# SuperCapV0.net
KiCad netlist of a schematic drawn in Altium Designer
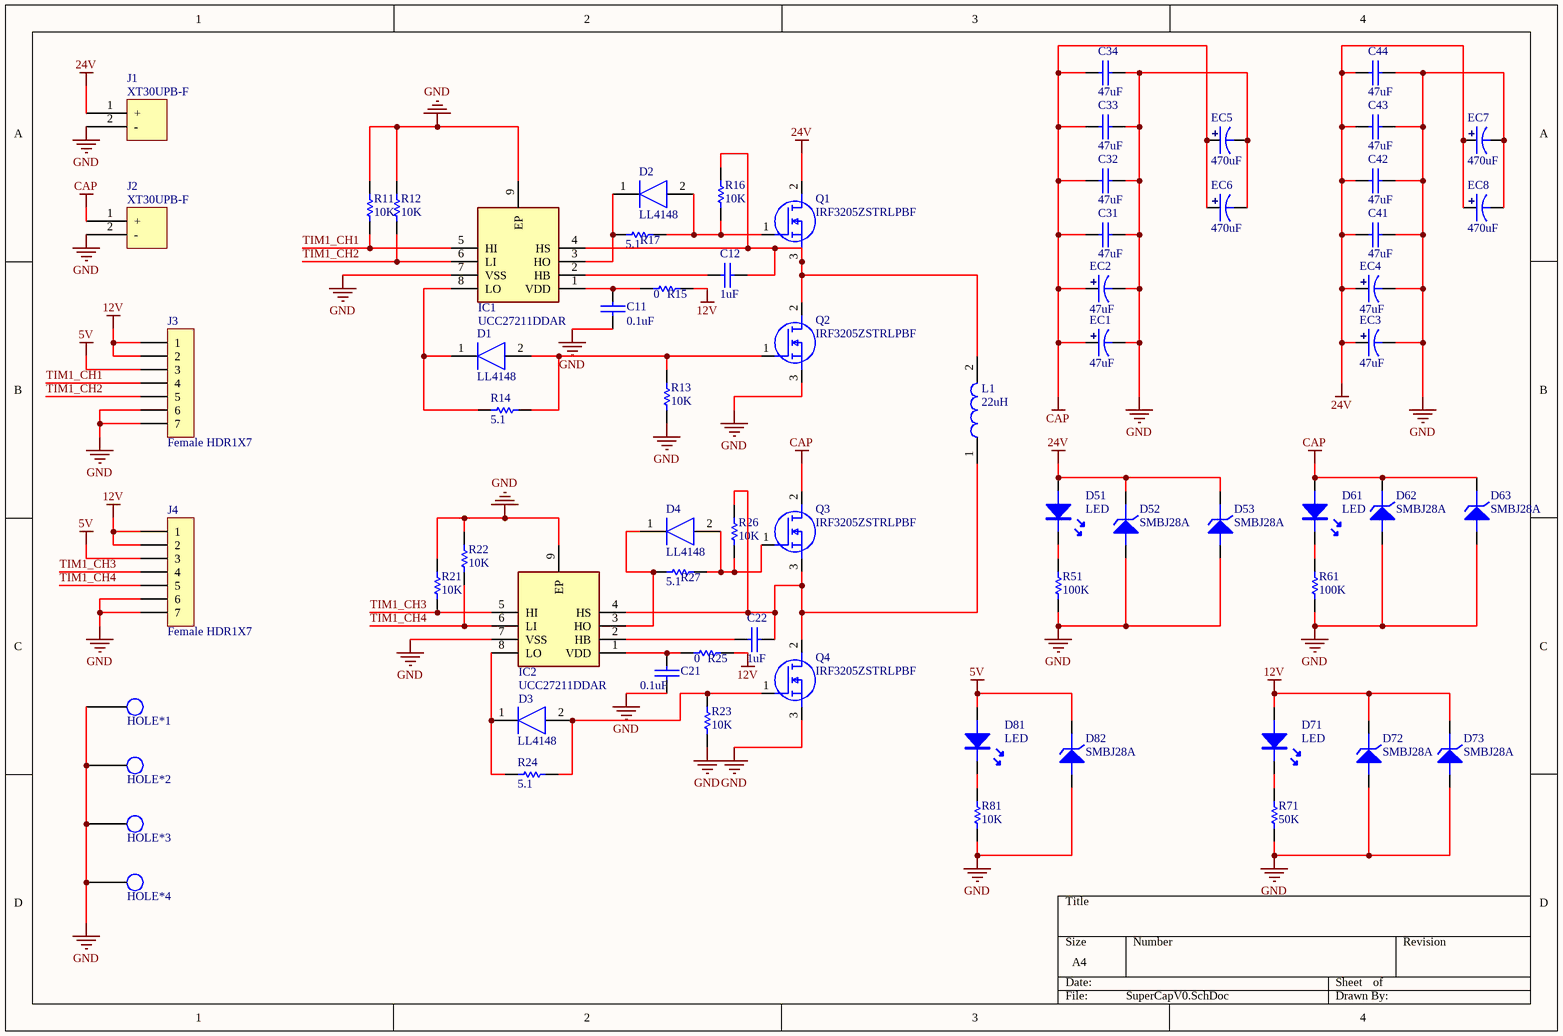
[diagram p0: SuperCapV0.SchDoc]

(export (version "E")
  (design (tool "Eeschema 10.0.6"))
  (components
    (comp (ref "C11")
      (value "0.1uF")
      (footprint "0603C")
      (description "无极性电容")
      (libsource (lib "电容") (part "CAP"))
    )
    (comp (ref "C12")
      (value "1uF")
      (footprint "0603C")
      (description "无极性电容")
      (libsource (lib "电容") (part "CAP"))
    )
    (comp (ref "C21")
      (value "0.1uF")
      (footprint "0603C")
      (description "无极性电容")
      (libsource (lib "电容") (part "CAP"))
    )
    (comp (ref "C22")
      (value "1uF")
      (footprint "0603C")
      (description "无极性电容")
      (libsource (lib "电容") (part "CAP"))
    )
    (comp (ref "C31")
      (value "47uF")
      (footprint "1812C")
      (description "无极性电容")
      (libsource (lib "电容") (part "CAP"))
    )
    (comp (ref "C32")
      (value "47uF")
      (footprint "1812C")
      (description "无极性电容")
      (libsource (lib "电容") (part "CAP"))
    )
    (comp (ref "C33")
      (value "47uF")
      (footprint "1812C")
      (description "无极性电容")
      (libsource (lib "电容") (part "CAP"))
    )
    (comp (ref "C34")
      (value "47uF")
      (footprint "1812C")
      (description "无极性电容")
      (libsource (lib "电容") (part "CAP"))
    )
    (comp (ref "C41")
      (value "47uF")
      (footprint "1812C")
      (description "无极性电容")
      (libsource (lib "电容") (part "CAP"))
    )
    (comp (ref "C42")
      (value "47uF")
      (footprint "1812C")
      (description "无极性电容")
      (libsource (lib "电容") (part "CAP"))
    )
    (comp (ref "C43")
      (value "47uF")
      (footprint "1812C")
      (description "无极性电容")
      (libsource (lib "电容") (part "CAP"))
    )
    (comp (ref "C44")
      (value "47uF")
      (footprint "1812C")
      (description "无极性电容")
      (libsource (lib "电容") (part "CAP"))
    )
    (comp (ref "D1")
      (value "LL4148")
      (footprint "SamacSys:FDLL4448")
      (description "Diode")
      (fields (field (name "MOUSER PART NUMBER") "512-LL4148"))
      (libsource (lib "*") (part "LL4148"))
    )
    (comp (ref "D2")
      (value "LL4148")
      (footprint "SamacSys:FDLL4448")
      (description "Diode")
      (fields (field (name "MOUSER PART NUMBER") "512-LL4148"))
      (libsource (lib "*") (part "LL4148"))
    )
    (comp (ref "D3")
      (value "LL4148")
      (footprint "SamacSys:FDLL4448")
      (description "Diode")
      (fields (field (name "MOUSER PART NUMBER") "512-LL4148"))
      (libsource (lib "*") (part "LL4148"))
    )
    (comp (ref "D4")
      (value "LL4148")
      (footprint "SamacSys:FDLL4448")
      (description "Diode")
      (fields (field (name "MOUSER PART NUMBER") "512-LL4148"))
      (libsource (lib "*") (part "LL4148"))
    )
    (comp (ref "D51") (value "LED") (footprint "LED-0603G") (libsource (lib "SuperCap_V2") (part "LED")))
    (comp (ref "D52")
      (value "SMBJ28A")
      (footprint "SMC/DO-214AB")
      (description "稳压二极管")
      (libsource (lib "二极管") (part "DIODE ZENER"))
    )
    (comp (ref "D53")
      (value "SMBJ28A")
      (footprint "SMC/DO-214AB")
      (description "稳压二极管")
      (libsource (lib "二极管") (part "DIODE ZENER"))
    )
    (comp (ref "D61") (value "LED") (footprint "LED-0603G") (libsource (lib "SuperCap_V2") (part "LED")))
    (comp (ref "D62")
      (value "SMBJ28A")
      (footprint "SMC/DO-214AB")
      (description "稳压二极管")
      (libsource (lib "二极管") (part "DIODE ZENER"))
    )
    (comp (ref "D63")
      (value "SMBJ28A")
      (footprint "SMC/DO-214AB")
      (description "稳压二极管")
      (libsource (lib "二极管") (part "DIODE ZENER"))
    )
    (comp (ref "D71") (value "LED") (footprint "LED-0603G") (libsource (lib "SuperCap_V2") (part "LED")))
    (comp (ref "D72")
      (value "SMBJ28A")
      (footprint "SMC/DO-214AB")
      (description "稳压二极管")
      (libsource (lib "二极管") (part "DIODE ZENER"))
    )
    (comp (ref "D73")
      (value "SMBJ28A")
      (footprint "SMC/DO-214AB")
      (description "稳压二极管")
      (libsource (lib "二极管") (part "DIODE ZENER"))
    )
    (comp (ref "D81") (value "LED") (footprint "LED-0603G") (libsource (lib "SuperCap_V2") (part "LED")))
    (comp (ref "D82")
      (value "SMBJ28A")
      (footprint "SMC/DO-214AB")
      (description "稳压二极管")
      (libsource (lib "二极管") (part "DIODE ZENER"))
    )
    (comp (ref "EC1")
      (value "47uF")
      (footprint "SMD-EC10X10X10")
      (description "贴片电解电容")
      (libsource (lib "电容") (part "SMD_ECAP"))
    )
    (comp (ref "EC2")
      (value "47uF")
      (footprint "SMD-EC10X10X10")
      (description "贴片电解电容")
      (libsource (lib "电容") (part "SMD_ECAP"))
    )
    (comp (ref "EC3")
      (value "47uF")
      (footprint "SMD-EC10X10X10")
      (description "贴片电解电容")
      (libsource (lib "电容") (part "SMD_ECAP"))
    )
    (comp (ref "EC4")
      (value "47uF")
      (footprint "SMD-EC10X10X10")
      (description "贴片电解电容")
      (libsource (lib "电容") (part "SMD_ECAP"))
    )
    (comp (ref "EC5")
      (value "470uF")
      (footprint "DIP-EC5.0X10X16-A")
      (description "直插电解电容")
      (libsource (lib "电容") (part "DIP_ECAP"))
    )
    (comp (ref "EC6")
      (value "470uF")
      (footprint "DIP-EC5.0X10X16-A")
      (description "直插电解电容")
      (libsource (lib "电容") (part "DIP_ECAP"))
    )
    (comp (ref "EC7")
      (value "470uF")
      (footprint "DIP-EC5.0X10X16-A")
      (description "直插电解电容")
      (libsource (lib "电容") (part "DIP_ECAP"))
    )
    (comp (ref "EC8")
      (value "470uF")
      (footprint "DIP-EC5.0X10X16-A")
      (description "直插电解电容")
      (libsource (lib "电容") (part "DIP_ECAP"))
    )
    (comp (ref "HOLE*1") (value "Hole") (footprint "M3") (libsource (lib "SuperCap_V2") (part "Hole")))
    (comp (ref "HOLE*2") (value "Hole") (footprint "M3") (libsource (lib "SuperCap_V2") (part "Hole")))
    (comp (ref "HOLE*3") (value "Hole") (footprint "M3") (libsource (lib "SuperCap_V2") (part "Hole")))
    (comp (ref "HOLE*4") (value "Hole") (footprint "M3") (libsource (lib "SuperCap_V2") (part "Hole")))
    (comp (ref "IC1")
      (value "UCC27211DDAR")
      (footprint "SamacSys:SOIC127P600X170-9N")
      (description "Integrated Circuit")
      (fields (field (name "MOUSER PART NUMBER") "595-UCC27211DDAR"))
      (libsource (lib "SamacSys") (part "UCC27211DDAR"))
    )
    (comp (ref "IC2")
      (value "UCC27211DDAR")
      (footprint "SamacSys:SOIC127P600X170-9N")
      (description "Integrated Circuit")
      (fields (field (name "MOUSER PART NUMBER") "595-UCC27211DDAR"))
      (libsource (lib "SamacSys") (part "UCC27211DDAR"))
    )
    (comp (ref "J1")
      (value "XT30UPB-F")
      (footprint "XT30UPB-F")
      (libsource (lib "powerdesigner") (part "XT30UPB-F"))
    )
    (comp (ref "J2")
      (value "XT30UPB-F")
      (footprint "XT30UPB-F")
      (libsource (lib "powerdesigner") (part "XT30UPB-F"))
    )
    (comp (ref "J3")
      (value "Female HDR1X7")
      (footprint "Fe-HDR1X7/2.54-S")
      (libsource (lib "排母") (part "Female HDR1X7"))
    )
    (comp (ref "J4")
      (value "Female HDR1X7")
      (footprint "Fe-HDR1X7/2.54-S")
      (libsource (lib "排母") (part "Female HDR1X7"))
    )
    (comp (ref "L1")
      (value "22uH")
      (footprint "SamacSys:INDPM180170X700N")
      (description "Inductor")
      (fields (field (name "MANUFACTURER_PART_NUMBER") "BCIHP1770-100M"))
      (libsource (lib "SuperCap_V2") (part "BCIHP1770-100M"))
    )
    (comp (ref "Q1")
      (value "IRF3205ZSTRLPBF")
      (footprint "SamacSys:IDB30E60")
      (description "MOSFET (N-Channel)")
      (fields (field (name "MOUSER PART NUMBER") "942-IRF3205ZSTRLPBF"))
      (libsource (lib "SamacSys") (part "IRF3205ZSTRLPBF"))
    )
    (comp (ref "Q2")
      (value "IRF3205ZSTRLPBF")
      (footprint "SamacSys:IDB30E60")
      (description "MOSFET (N-Channel)")
      (fields (field (name "MOUSER PART NUMBER") "942-IRF3205ZSTRLPBF"))
      (libsource (lib "SamacSys") (part "IRF3205ZSTRLPBF"))
    )
    (comp (ref "Q3")
      (value "IRF3205ZSTRLPBF")
      (footprint "SamacSys:IDB30E60")
      (description "MOSFET (N-Channel)")
      (fields (field (name "MOUSER PART NUMBER") "942-IRF3205ZSTRLPBF"))
      (libsource (lib "SamacSys") (part "IRF3205ZSTRLPBF"))
    )
    (comp (ref "Q4")
      (value "IRF3205ZSTRLPBF")
      (footprint "SamacSys:IDB30E60")
      (description "MOSFET (N-Channel)")
      (fields (field (name "MOUSER PART NUMBER") "942-IRF3205ZSTRLPBF"))
      (libsource (lib "SamacSys") (part "IRF3205ZSTRLPBF"))
    )
    (comp (ref "R11") (value "10K") (footprint "0603R") (libsource (lib "电阻") (part "RES")))
    (comp (ref "R12") (value "10K") (footprint "0603R") (libsource (lib "电阻") (part "RES")))
    (comp (ref "R13") (value "10K") (footprint "0603R") (libsource (lib "电阻") (part "RES")))
    (comp (ref "R14") (value "5.1") (footprint "0603R") (libsource (lib "电阻") (part "RES")))
    (comp (ref "R15") (value "0") (footprint "0603R") (libsource (lib "电阻") (part "RES")))
    (comp (ref "R16") (value "10K") (footprint "0603R") (libsource (lib "电阻") (part "RES")))
    (comp (ref "R17") (value "5.1") (footprint "0603R") (libsource (lib "电阻") (part "RES")))
    (comp (ref "R21") (value "10K") (footprint "0603R") (libsource (lib "电阻") (part "RES")))
    (comp (ref "R22") (value "10K") (footprint "0603R") (libsource (lib "电阻") (part "RES")))
    (comp (ref "R23") (value "10K") (footprint "0603R") (libsource (lib "电阻") (part "RES")))
    (comp (ref "R24") (value "5.1") (footprint "0603R") (libsource (lib "电阻") (part "RES")))
    (comp (ref "R25") (value "0") (footprint "0603R") (libsource (lib "电阻") (part "RES")))
    (comp (ref "R26") (value "10K") (footprint "0603R") (libsource (lib "电阻") (part "RES")))
    (comp (ref "R27") (value "5.1") (footprint "0603R") (libsource (lib "电阻") (part "RES")))
    (comp (ref "R51") (value "100K") (footprint "0603R") (libsource (lib "电阻") (part "RES")))
    (comp (ref "R61") (value "100K") (footprint "0603R") (libsource (lib "电阻") (part "RES")))
    (comp (ref "R71") (value "50K") (footprint "0603R") (libsource (lib "电阻") (part "RES")))
    (comp (ref "R81") (value "10K") (footprint "0603R") (libsource (lib "电阻") (part "RES")))
  )
  (nets
    (net (code "1") (name "/TIM1_CH1") (class "Default")
      (node (ref "IC1") (pin "5") (pinfunction "HI_5") (pintype "passive"))
      (node (ref "J3") (pin "4") (pinfunction "4_4") (pintype "passive"))
      (node (ref "R11") (pin "1") (pinfunction "1_1") (pintype "passive"))
    )
    (net (code "2") (name "/TIM1_CH2") (class "Default")
      (node (ref "IC1") (pin "6") (pinfunction "LI_6") (pintype "passive"))
      (node (ref "J3") (pin "5") (pinfunction "5_5") (pintype "passive"))
      (node (ref "R12") (pin "1") (pinfunction "1_1") (pintype "passive"))
    )
    (net (code "3") (name "/TIM1_CH3") (class "Default")
      (node (ref "IC2") (pin "5") (pinfunction "HI_5") (pintype "passive"))
      (node (ref "J4") (pin "4") (pinfunction "4_4") (pintype "passive"))
      (node (ref "R21") (pin "1") (pinfunction "1_1") (pintype "passive"))
    )
    (net (code "4") (name "/TIM1_CH4") (class "Default")
      (node (ref "IC2") (pin "6") (pinfunction "LI_6") (pintype "passive"))
      (node (ref "J4") (pin "5") (pinfunction "5_5") (pintype "passive"))
      (node (ref "R22") (pin "1") (pinfunction "1_1") (pintype "passive"))
    )
    (net (code "5") (name "5V") (class "Default")
      (node (ref "D81") (pin "A") (pinfunction "A_A") (pintype "passive"))
      (node (ref "D82") (pin "K") (pinfunction "K_K") (pintype "passive"))
      (node (ref "J3") (pin "3") (pinfunction "3_3") (pintype "passive"))
      (node (ref "J4") (pin "3") (pinfunction "3_3") (pintype "passive"))
    )
    (net (code "6") (name "12V") (class "Default")
      (node (ref "D71") (pin "A") (pinfunction "A_A") (pintype "passive"))
      (node (ref "D72") (pin "K") (pinfunction "K_K") (pintype "passive"))
      (node (ref "D73") (pin "K") (pinfunction "K_K") (pintype "passive"))
      (node (ref "J3") (pin "1") (pinfunction "1_1") (pintype "passive"))
      (node (ref "J3") (pin "2") (pinfunction "2_2") (pintype "passive"))
      (node (ref "J4") (pin "1") (pinfunction "1_1") (pintype "passive"))
      (node (ref "J4") (pin "2") (pinfunction "2_2") (pintype "passive"))
      (node (ref "R15") (pin "2") (pinfunction "2_2") (pintype "passive"))
      (node (ref "R25") (pin "2") (pinfunction "2_2") (pintype "passive"))
    )
    (net (code "7") (name "24V") (class "Default")
      (node (ref "C41") (pin "1") (pinfunction "1_1") (pintype "passive"))
      (node (ref "C42") (pin "1") (pinfunction "1_1") (pintype "passive"))
      (node (ref "C43") (pin "1") (pinfunction "1_1") (pintype "passive"))
      (node (ref "C44") (pin "1") (pinfunction "1_1") (pintype "passive"))
      (node (ref "D51") (pin "A") (pinfunction "A_A") (pintype "passive"))
      (node (ref "D52") (pin "K") (pinfunction "K_K") (pintype "passive"))
      (node (ref "D53") (pin "K") (pinfunction "K_K") (pintype "passive"))
      (node (ref "EC3") (pin "1") (pinfunction "1_1") (pintype "passive"))
      (node (ref "EC4") (pin "1") (pinfunction "1_1") (pintype "passive"))
      (node (ref "EC7") (pin "1") (pinfunction "1_1") (pintype "passive"))
      (node (ref "EC8") (pin "1") (pinfunction "1_1") (pintype "passive"))
      (node (ref "J1") (pin "1") (pinfunction "+_1") (pintype "passive"))
      (node (ref "Q1") (pin "2") (pinfunction "D_2") (pintype "passive"))
    )
    (net (code "8") (name "CAP") (class "Default")
      (node (ref "C31") (pin "1") (pinfunction "1_1") (pintype "passive"))
      (node (ref "C32") (pin "1") (pinfunction "1_1") (pintype "passive"))
      (node (ref "C33") (pin "1") (pinfunction "1_1") (pintype "passive"))
      (node (ref "C34") (pin "1") (pinfunction "1_1") (pintype "passive"))
      (node (ref "D61") (pin "A") (pinfunction "A_A") (pintype "passive"))
      (node (ref "D62") (pin "K") (pinfunction "K_K") (pintype "passive"))
      (node (ref "D63") (pin "K") (pinfunction "K_K") (pintype "passive"))
      (node (ref "EC1") (pin "1") (pinfunction "1_1") (pintype "passive"))
      (node (ref "EC2") (pin "1") (pinfunction "1_1") (pintype "passive"))
      (node (ref "EC5") (pin "1") (pinfunction "1_1") (pintype "passive"))
      (node (ref "EC6") (pin "1") (pinfunction "1_1") (pintype "passive"))
      (node (ref "J2") (pin "1") (pinfunction "+_1") (pintype "passive"))
      (node (ref "Q3") (pin "2") (pinfunction "D_2") (pintype "passive"))
    )
    (net (code "9") (name "GND") (class "Default")
      (node (ref "C11") (pin "1") (pinfunction "1_1") (pintype "passive"))
      (node (ref "C21") (pin "1") (pinfunction "1_1") (pintype "passive"))
      (node (ref "C31") (pin "2") (pinfunction "2_2") (pintype "passive"))
      (node (ref "C32") (pin "2") (pinfunction "2_2") (pintype "passive"))
      (node (ref "C33") (pin "2") (pinfunction "2_2") (pintype "passive"))
      (node (ref "C34") (pin "2") (pinfunction "2_2") (pintype "passive"))
      (node (ref "C41") (pin "2") (pinfunction "2_2") (pintype "passive"))
      (node (ref "C42") (pin "2") (pinfunction "2_2") (pintype "passive"))
      (node (ref "C43") (pin "2") (pinfunction "2_2") (pintype "passive"))
      (node (ref "C44") (pin "2") (pinfunction "2_2") (pintype "passive"))
      (node (ref "D52") (pin "A") (pinfunction "A_A") (pintype "passive"))
      (node (ref "D53") (pin "A") (pinfunction "A_A") (pintype "passive"))
      (node (ref "D62") (pin "A") (pinfunction "A_A") (pintype "passive"))
      (node (ref "D63") (pin "A") (pinfunction "A_A") (pintype "passive"))
      (node (ref "D72") (pin "A") (pinfunction "A_A") (pintype "passive"))
      (node (ref "D73") (pin "A") (pinfunction "A_A") (pintype "passive"))
      (node (ref "D82") (pin "A") (pinfunction "A_A") (pintype "passive"))
      (node (ref "EC1") (pin "2") (pinfunction "2_2") (pintype "passive"))
      (node (ref "EC2") (pin "2") (pinfunction "2_2") (pintype "passive"))
      (node (ref "EC3") (pin "2") (pinfunction "2_2") (pintype "passive"))
      (node (ref "EC4") (pin "2") (pinfunction "2_2") (pintype "passive"))
      (node (ref "EC5") (pin "2") (pinfunction "2_2") (pintype "passive"))
      (node (ref "EC6") (pin "2") (pinfunction "2_2") (pintype "passive"))
      (node (ref "EC7") (pin "2") (pinfunction "2_2") (pintype "passive"))
      (node (ref "EC8") (pin "2") (pinfunction "2_2") (pintype "passive"))
      (node (ref "HOLE*1") (pin "1") (pinfunction "1_1") (pintype "passive"))
      (node (ref "HOLE*2") (pin "1") (pinfunction "1_1") (pintype "passive"))
      (node (ref "HOLE*3") (pin "1") (pinfunction "1_1") (pintype "passive"))
      (node (ref "HOLE*4") (pin "1") (pinfunction "1_1") (pintype "passive"))
      (node (ref "IC1") (pin "7") (pinfunction "VSS_7") (pintype "passive"))
      (node (ref "IC1") (pin "9") (pinfunction "EP_9") (pintype "passive"))
      (node (ref "IC2") (pin "7") (pinfunction "VSS_7") (pintype "passive"))
      (node (ref "IC2") (pin "9") (pinfunction "EP_9") (pintype "passive"))
      (node (ref "J1") (pin "2") (pinfunction "-_2") (pintype "passive"))
      (node (ref "J2") (pin "2") (pinfunction "-_2") (pintype "passive"))
      (node (ref "J3") (pin "6") (pinfunction "6_6") (pintype "passive"))
      (node (ref "J3") (pin "7") (pinfunction "7_7") (pintype "passive"))
      (node (ref "J4") (pin "6") (pinfunction "6_6") (pintype "passive"))
      (node (ref "J4") (pin "7") (pinfunction "7_7") (pintype "passive"))
      (node (ref "Q2") (pin "3") (pinfunction "S_3") (pintype "passive"))
      (node (ref "Q4") (pin "3") (pinfunction "S_3") (pintype "passive"))
      (node (ref "R11") (pin "2") (pinfunction "2_2") (pintype "passive"))
      (node (ref "R12") (pin "2") (pinfunction "2_2") (pintype "passive"))
      (node (ref "R13") (pin "1") (pinfunction "1_1") (pintype "passive"))
      (node (ref "R21") (pin "2") (pinfunction "2_2") (pintype "passive"))
      (node (ref "R22") (pin "2") (pinfunction "2_2") (pintype "passive"))
      (node (ref "R23") (pin "1") (pinfunction "1_1") (pintype "passive"))
      (node (ref "R51") (pin "1") (pinfunction "1_1") (pintype "passive"))
      (node (ref "R61") (pin "1") (pinfunction "1_1") (pintype "passive"))
      (node (ref "R71") (pin "1") (pinfunction "1_1") (pintype "passive"))
      (node (ref "R81") (pin "1") (pinfunction "1_1") (pintype "passive"))
    )
    (net (code "10") (name "Net-(D1-A)") (class "Default")
      (node (ref "D1") (pin "2") (pinfunction "A_2") (pintype "passive"))
      (node (ref "Q2") (pin "1") (pinfunction "G_1") (pintype "passive"))
      (node (ref "R13") (pin "2") (pinfunction "2_2") (pintype "passive"))
      (node (ref "R14") (pin "2") (pinfunction "2_2") (pintype "passive"))
    )
    (net (code "11") (name "Net-(D1-K)") (class "Default")
      (node (ref "D1") (pin "1") (pinfunction "K_1") (pintype "passive"))
      (node (ref "IC1") (pin "8") (pinfunction "LO_8") (pintype "passive"))
      (node (ref "R14") (pin "1") (pinfunction "1_1") (pintype "passive"))
    )
    (net (code "12") (name "Net-(D2-A)") (class "Default")
      (node (ref "D2") (pin "2") (pinfunction "A_2") (pintype "passive"))
      (node (ref "Q1") (pin "1") (pinfunction "G_1") (pintype "passive"))
      (node (ref "R16") (pin "1") (pinfunction "1_1") (pintype "passive"))
      (node (ref "R17") (pin "2") (pinfunction "2_2") (pintype "passive"))
    )
    (net (code "13") (name "Net-(D2-K)") (class "Default")
      (node (ref "D2") (pin "1") (pinfunction "K_1") (pintype "passive"))
      (node (ref "IC1") (pin "3") (pinfunction "HO_3") (pintype "passive"))
      (node (ref "R17") (pin "1") (pinfunction "1_1") (pintype "passive"))
    )
    (net (code "14") (name "Net-(D3-A)") (class "Default")
      (node (ref "D3") (pin "2") (pinfunction "A_2") (pintype "passive"))
      (node (ref "Q4") (pin "1") (pinfunction "G_1") (pintype "passive"))
      (node (ref "R23") (pin "2") (pinfunction "2_2") (pintype "passive"))
      (node (ref "R24") (pin "2") (pinfunction "2_2") (pintype "passive"))
    )
    (net (code "15") (name "Net-(D3-K)") (class "Default")
      (node (ref "D3") (pin "1") (pinfunction "K_1") (pintype "passive"))
      (node (ref "IC2") (pin "8") (pinfunction "LO_8") (pintype "passive"))
      (node (ref "R24") (pin "1") (pinfunction "1_1") (pintype "passive"))
    )
    (net (code "16") (name "Net-(D4-A)") (class "Default")
      (node (ref "D4") (pin "2") (pinfunction "A_2") (pintype "passive"))
      (node (ref "Q3") (pin "1") (pinfunction "G_1") (pintype "passive"))
      (node (ref "R26") (pin "1") (pinfunction "1_1") (pintype "passive"))
      (node (ref "R27") (pin "2") (pinfunction "2_2") (pintype "passive"))
    )
    (net (code "17") (name "Net-(D4-K)") (class "Default")
      (node (ref "D4") (pin "1") (pinfunction "K_1") (pintype "passive"))
      (node (ref "IC2") (pin "3") (pinfunction "HO_3") (pintype "passive"))
      (node (ref "R27") (pin "1") (pinfunction "1_1") (pintype "passive"))
    )
    (net (code "18") (name "Net-(D51-PadK)") (class "Default")
      (node (ref "D51") (pin "K") (pinfunction "K_K") (pintype "passive"))
      (node (ref "R51") (pin "2") (pinfunction "2_2") (pintype "passive"))
    )
    (net (code "19") (name "Net-(D61-PadK)") (class "Default")
      (node (ref "D61") (pin "K") (pinfunction "K_K") (pintype "passive"))
      (node (ref "R61") (pin "2") (pinfunction "2_2") (pintype "passive"))
    )
    (net (code "20") (name "Net-(D71-PadK)") (class "Default")
      (node (ref "D71") (pin "K") (pinfunction "K_K") (pintype "passive"))
      (node (ref "R71") (pin "2") (pinfunction "2_2") (pintype "passive"))
    )
    (net (code "21") (name "Net-(D81-PadK)") (class "Default")
      (node (ref "D81") (pin "K") (pinfunction "K_K") (pintype "passive"))
      (node (ref "R81") (pin "2") (pinfunction "2_2") (pintype "passive"))
    )
    (net (code "22") (name "Net-(IC1-HB)") (class "Default")
      (node (ref "C12") (pin "2") (pinfunction "2_2") (pintype "passive"))
      (node (ref "IC1") (pin "2") (pinfunction "HB_2") (pintype "passive"))
    )
    (net (code "23") (name "Net-(IC1-HS)") (class "Default")
      (node (ref "C12") (pin "1") (pinfunction "1_1") (pintype "passive"))
      (node (ref "IC1") (pin "4") (pinfunction "HS_4") (pintype "passive"))
      (node (ref "L1") (pin "2") (pinfunction "2_2") (pintype "passive"))
      (node (ref "Q1") (pin "3") (pinfunction "S_3") (pintype "passive"))
      (node (ref "Q2") (pin "2") (pinfunction "D_2") (pintype "passive"))
      (node (ref "R16") (pin "2") (pinfunction "2_2") (pintype "passive"))
    )
    (net (code "24") (name "Net-(IC1-VDD)") (class "Default")
      (node (ref "C11") (pin "2") (pinfunction "2_2") (pintype "passive"))
      (node (ref "IC1") (pin "1") (pinfunction "VDD_1") (pintype "passive"))
      (node (ref "R15") (pin "1") (pinfunction "1_1") (pintype "passive"))
    )
    (net (code "25") (name "Net-(IC2-HB)") (class "Default")
      (node (ref "C22") (pin "2") (pinfunction "2_2") (pintype "passive"))
      (node (ref "IC2") (pin "2") (pinfunction "HB_2") (pintype "passive"))
    )
    (net (code "26") (name "Net-(IC2-HS)") (class "Default")
      (node (ref "C22") (pin "1") (pinfunction "1_1") (pintype "passive"))
      (node (ref "IC2") (pin "4") (pinfunction "HS_4") (pintype "passive"))
      (node (ref "L1") (pin "1") (pinfunction "1_1") (pintype "passive"))
      (node (ref "Q3") (pin "3") (pinfunction "S_3") (pintype "passive"))
      (node (ref "Q4") (pin "2") (pinfunction "D_2") (pintype "passive"))
      (node (ref "R26") (pin "2") (pinfunction "2_2") (pintype "passive"))
    )
    (net (code "27") (name "Net-(IC2-VDD)") (class "Default")
      (node (ref "C21") (pin "2") (pinfunction "2_2") (pintype "passive"))
      (node (ref "IC2") (pin "1") (pinfunction "VDD_1") (pintype "passive"))
      (node (ref "R25") (pin "1") (pinfunction "1_1") (pintype "passive"))
    )
  )
)
